# design.net
KiCad netlist of a schematic drawn in Altium Designer
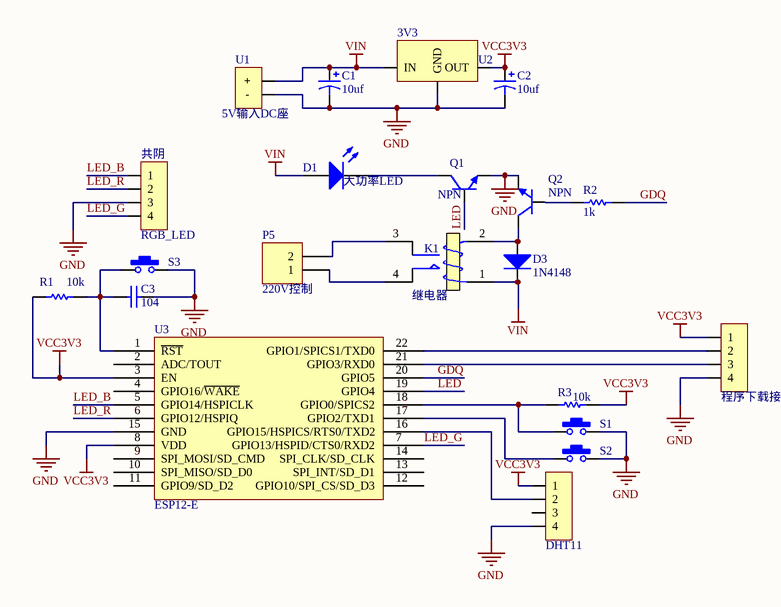
[diagram p0: 电路图.SchDoc]

(export (version "E")
  (design (tool "Eeschema 10.0.6"))
  (components
    (comp (ref "C1")
      (value "CAP0")
      (footprint "3528 钽电容")
      (description "电解电容")
      (fields (field (name "ALTIUM_UNNAMED_1") "10uf"))
      (libsource (lib "schematic_library") (part "CAP0"))
    )
    (comp (ref "C2")
      (value "CAP0")
      (footprint "3528 钽电容")
      (description "电解电容")
      (fields (field (name "ALTIUM_UNNAMED_1") "10uf"))
      (libsource (lib "schematic_library") (part "CAP0"))
    )
    (comp (ref "C3")
      (value "104")
      (footprint "0805-0C")
      (description "无极电容")
      (libsource (lib "schematic_library") (part "CAP1"))
    )
    (comp (ref "D1")
      (value "大功率LED")
      (footprint "3.5X2.8X1.9")
      (description "Typical BLUE SiC LED")
      (fields (field (name "PUBLISHER") "Altium Limited"))
      (libsource (lib "Miscellaneous Devices") (part "LED3"))
    )
    (comp (ref "D3") (value "1N4148") (footprint "二极管") (libsource (lib "原理图库") (part "二极管")))
    (comp (ref "DHT11")
      (value "下载接口")
      (footprint "XH2.54-4")
      (description "接线柱")
      (libsource (lib "schematic_library") (part "Header_4"))
    )
    (comp (ref "K1") (value "继电器") (footprint "继电器") (libsource (lib "原理图库") (part "继电器")))
    (comp (ref "P5")
      (value "220V控制")
      (footprint "HDR1X2")
      (description "Header, 2-Pin")
      (fields (field (name "PUBLISHER") "Altium Limited"))
      (libsource (lib "Miscellaneous Connectors") (part "Header 2"))
    )
    (comp (ref "Q1")
      (value "NPN")
      (footprint "SS8050")
      (description "9013、9014、8050")
      (libsource (lib "原理图库") (part "NPN"))
    )
    (comp (ref "Q2")
      (value "NPN")
      (footprint "SS8050")
      (description "9013、9014、8050")
      (libsource (lib "原理图库") (part "NPN"))
    )
    (comp (ref "R1")
      (value "RES")
      (footprint "0805-0R")
      (description "电阻")
      (fields (field (name "ALTIUM_UNNAMED_1") "10k"))
      (libsource (lib "schematic_library") (part "RES"))
    )
    (comp (ref "R2")
      (value "RES")
      (footprint "0805-0R")
      (description "电阻")
      (fields (field (name "ALTIUM_UNNAMED_1") "1k"))
      (libsource (lib "原理图库") (part "RES"))
    )
    (comp (ref "R3")
      (value "RES")
      (footprint "0805-0R")
      (description "电阻")
      (fields (field (name "ALTIUM_UNNAMED_1") "10k"))
      (libsource (lib "schematic_library") (part "RES"))
    )
    (comp (ref "RGB_LED")
      (value "共阴")
      (footprint "XH2.54-4")
      (description "接线柱")
      (libsource (lib "schematic_library") (part "Header_4"))
    )
    (comp (ref "S1")
      (value "KEY")
      (footprint "KEY-DIP4")
      (description "微动开关")
      (libsource (lib "schematic_library") (part "KEY"))
    )
    (comp (ref "S2")
      (value "KEY")
      (footprint "KEY-DIP4")
      (description "微动开关")
      (libsource (lib "schematic_library") (part "KEY"))
    )
    (comp (ref "S3")
      (value "KEY")
      (footprint "KEY-DIP4")
      (description "微动开关")
      (libsource (lib "schematic_library") (part "KEY"))
    )
    (comp (ref "U1")
      (value "5V输入DC座")
      (footprint "DC-PJ044A")
      (description "DC插座")
      (libsource (lib "schematic_library") (part "DC座"))
    )
    (comp (ref "U2")
      (value "3V3")
      (footprint "SOT-223")
      (description "降压稳压器贴SOT223片封装")
      (libsource (lib "schematic_library") (part "ASM1117"))
    )
    (comp (ref "U3")
      (value "ESP12-E")
      (footprint "ESP12-E")
      (description "ESP8266-E")
      (libsource (lib "schematic_library") (part "ESP12-E"))
    )
    (comp (ref "程序下载接口")
      (value "下载接口")
      (footprint "XH2.54-4")
      (description "接线柱")
      (libsource (lib "schematic_library") (part "Header_4"))
    )
  )
  (nets
    (net (code "1") (name "/GDQ") (class "Default")
      (node (ref "R2") (pin "1") (pinfunction "1_1") (pintype "passive"))
      (node (ref "U3") (pin "20") (pinfunction "GPIO5_20") (pintype "passive"))
    )
    (net (code "2") (name "/LED") (class "Default")
      (node (ref "Q1") (pin "B") (pinfunction "B_B") (pintype "passive"))
      (node (ref "U3") (pin "19") (pinfunction "GPIO4_19") (pintype "passive"))
    )
    (net (code "3") (name "/LED_B") (class "Default")
      (node (ref "RGB_LED") (pin "1") (pinfunction "1_1") (pintype "passive"))
      (node (ref "U3") (pin "5") (pinfunction "GPIO14/HSPICLK_5") (pintype "passive"))
    )
    (net (code "4") (name "/LED_G") (class "Default")
      (node (ref "RGB_LED") (pin "4") (pinfunction "4_4") (pintype "passive"))
      (node (ref "U3") (pin "7") (pinfunction "GPIO13/HSPID/CTS0/RXD2_7") (pintype "passive"))
    )
    (net (code "5") (name "/LED_R") (class "Default")
      (node (ref "RGB_LED") (pin "2") (pinfunction "2_2") (pintype "passive"))
      (node (ref "U3") (pin "6") (pinfunction "GPIO12/HSPIQ_6") (pintype "passive"))
    )
    (net (code "6") (name "GND") (class "Default")
      (node (ref "C1") (pin "2") (pinfunction "2_2") (pintype "passive"))
      (node (ref "C2") (pin "2") (pinfunction "2_2") (pintype "passive"))
      (node (ref "C3") (pin "1") (pinfunction "1_1") (pintype "passive"))
      (node (ref "DHT11") (pin "4") (pinfunction "4_4") (pintype "passive"))
      (node (ref "Q1") (pin "E") (pinfunction "E_E") (pintype "passive"))
      (node (ref "Q2") (pin "E") (pinfunction "E_E") (pintype "passive"))
      (node (ref "RGB_LED") (pin "3") (pinfunction "3_3") (pintype "passive"))
      (node (ref "S1") (pin "2") (pinfunction "2_2") (pintype "passive"))
      (node (ref "S2") (pin "2") (pinfunction "2_2") (pintype "passive"))
      (node (ref "S3") (pin "2") (pinfunction "2_2") (pintype "passive"))
      (node (ref "U1") (pin "1") (pinfunction "－_1") (pintype "passive"))
      (node (ref "U2") (pin "1") (pinfunction "GND_1") (pintype "passive"))
      (node (ref "U3") (pin "15") (pinfunction "GND_15") (pintype "passive"))
      (node (ref "程序下载接口") (pin "4") (pinfunction "4_4") (pintype "passive"))
    )
    (net (code "7") (name "Net-(D1-K)") (class "Default")
      (node (ref "D1") (pin "2") (pinfunction "K_2") (pintype "passive"))
      (node (ref "Q1") (pin "C") (pinfunction "C_C") (pintype "passive"))
    )
    (net (code "8") (name "Net-(D3-A)") (class "Default")
      (node (ref "D3") (pin "1") (pinfunction "A_1") (pintype "passive"))
      (node (ref "K1") (pin "2") (pinfunction "2_2") (pintype "passive"))
      (node (ref "Q2") (pin "C") (pinfunction "C_C") (pintype "passive"))
    )
    (net (code "9") (name "Net-(K1-Pad3)") (class "Default")
      (node (ref "K1") (pin "3") (pinfunction "3_3") (pintype "passive"))
      (node (ref "P5") (pin "2") (pinfunction "2_2") (pintype "passive"))
    )
    (net (code "10") (name "Net-(K1-Pad4)") (class "Default")
      (node (ref "K1") (pin "4") (pinfunction "4_4") (pintype "passive"))
      (node (ref "P5") (pin "1") (pinfunction "1_1") (pintype "passive"))
    )
    (net (code "11") (name "Net-(Q2-PadB)") (class "Default")
      (node (ref "Q2") (pin "B") (pinfunction "B_B") (pintype "passive"))
      (node (ref "R2") (pin "2") (pinfunction "2_2") (pintype "passive"))
    )
    (net (code "12") (name "Net-(U3-GPIO0{slash}SPICS2)") (class "Default")
      (node (ref "R3") (pin "2") (pinfunction "2_2") (pintype "passive"))
      (node (ref "S1") (pin "1") (pinfunction "1_1") (pintype "passive"))
      (node (ref "U3") (pin "18") (pinfunction "GPIO0/SPICS2_18") (pintype "passive"))
    )
    (net (code "13") (name "Net-(U3-GPIO1{slash}SPICS1{slash}TXD0)") (class "Default")
      (node (ref "U3") (pin "22") (pinfunction "GPIO1/SPICS1/TXD0_22") (pintype "passive"))
      (node (ref "程序下载接口") (pin "2") (pinfunction "2_2") (pintype "passive"))
    )
    (net (code "14") (name "Net-(U3-GPIO2{slash}TXD1)") (class "Default")
      (node (ref "S2") (pin "1") (pinfunction "1_1") (pintype "passive"))
      (node (ref "U3") (pin "17") (pinfunction "GPIO2/TXD1_17") (pintype "passive"))
    )
    (net (code "15") (name "Net-(U3-GPIO3{slash}RXD0)") (class "Default")
      (node (ref "U3") (pin "21") (pinfunction "GPIO3/RXD0_21") (pintype "passive"))
      (node (ref "程序下载接口") (pin "3") (pinfunction "3_3") (pintype "passive"))
    )
    (net (code "16") (name "Net-(U3-GPIO15{slash}HSPICS{slash}RTS0{slash}TXD2)") (class "Default")
      (node (ref "DHT11") (pin "2") (pinfunction "2_2") (pintype "passive"))
      (node (ref "U3") (pin "16") (pinfunction "GPIO15/HSPICS/RTS0/TXD2_16") (pintype "passive"))
    )
    (net (code "17") (name "Net-(U3-~{RST})") (class "Default")
      (node (ref "C3") (pin "2") (pinfunction "2_2") (pintype "passive"))
      (node (ref "R1") (pin "2") (pinfunction "2_2") (pintype "passive"))
      (node (ref "S3") (pin "1") (pinfunction "1_1") (pintype "passive"))
      (node (ref "U3") (pin "1") (pinfunction "~{RST}_1") (pintype "passive"))
    )
    (net (code "18") (name "VCC3V3") (class "Default")
      (node (ref "C2") (pin "1") (pinfunction "1_1") (pintype "passive"))
      (node (ref "DHT11") (pin "1") (pinfunction "1_1") (pintype "passive"))
      (node (ref "R1") (pin "1") (pinfunction "1_1") (pintype "passive"))
      (node (ref "R3") (pin "1") (pinfunction "1_1") (pintype "passive"))
      (node (ref "U2") (pin "2") (pinfunction "OUT_2") (pintype "passive"))
      (node (ref "U3") (pin "3") (pinfunction "EN_3") (pintype "passive"))
      (node (ref "U3") (pin "8") (pinfunction "VDD_8") (pintype "passive"))
      (node (ref "程序下载接口") (pin "1") (pinfunction "1_1") (pintype "passive"))
    )
    (net (code "19") (name "VIN") (class "Default")
      (node (ref "C1") (pin "1") (pinfunction "1_1") (pintype "passive"))
      (node (ref "D1") (pin "1") (pinfunction "A_1") (pintype "passive"))
      (node (ref "D3") (pin "2") (pinfunction "K_2") (pintype "passive"))
      (node (ref "K1") (pin "1") (pinfunction "1_1") (pintype "passive"))
      (node (ref "U1") (pin "2") (pinfunction "＋_2") (pintype "passive"))
      (node (ref "U2") (pin "3") (pinfunction "IN_3") (pintype "passive"))
    )
    (net (code "20") (name "unconnected-(DHT11-Pad3)") (class "Default")
      (node (ref "DHT11") (pin "3") (pinfunction "3_3") (pintype "passive"))
    )
    (net (code "21") (name "unconnected-(U3-ADC{slash}TOUT-Pad2)") (class "Default")
      (node (ref "U3") (pin "2") (pinfunction "ADC/TOUT_2") (pintype "passive"))
    )
    (net (code "22") (name "unconnected-(U3-GPIO9{slash}SD_D2-Pad11)") (class "Default")
      (node (ref "U3") (pin "11") (pinfunction "GPIO9/SD_D2_11") (pintype "passive"))
    )
    (net (code "23") (name "unconnected-(U3-GPIO10{slash}SPI_CS{slash}SD_D3-Pad12)") (class "Default")
      (node (ref "U3") (pin "12") (pinfunction "GPIO10/SPI_CS/SD_D3_12") (pintype "passive"))
    )
    (net (code "24") (name "unconnected-(U3-GPIO16{slash}~{WAKE}-Pad4)") (class "Default")
      (node (ref "U3") (pin "4") (pinfunction "GPIO16/~{WAKE}_4") (pintype "passive"))
    )
    (net (code "25") (name "unconnected-(U3-SPI_CLK{slash}SD_CLK-Pad14)") (class "Default")
      (node (ref "U3") (pin "14") (pinfunction "SPI_CLK/SD_CLK_14") (pintype "passive"))
    )
    (net (code "26") (name "unconnected-(U3-SPI_INT{slash}SD_D1-Pad13)") (class "Default")
      (node (ref "U3") (pin "13") (pinfunction "SPI_INT/SD_D1_13") (pintype "passive"))
    )
    (net (code "27") (name "unconnected-(U3-SPI_MISO{slash}SD_D0-Pad10)") (class "Default")
      (node (ref "U3") (pin "10") (pinfunction "SPI_MISO/SD_D0_10") (pintype "passive"))
    )
    (net (code "28") (name "unconnected-(U3-SPI_MOSI{slash}SD_CMD-Pad9)") (class "Default")
      (node (ref "U3") (pin "9") (pinfunction "SPI_MOSI/SD_CMD_9") (pintype "passive"))
    )
  )
)
